# SCH_KSGER_T12_STM32_2023-10-02.net
KiCad netlist of a schematic drawn in EasyEDA
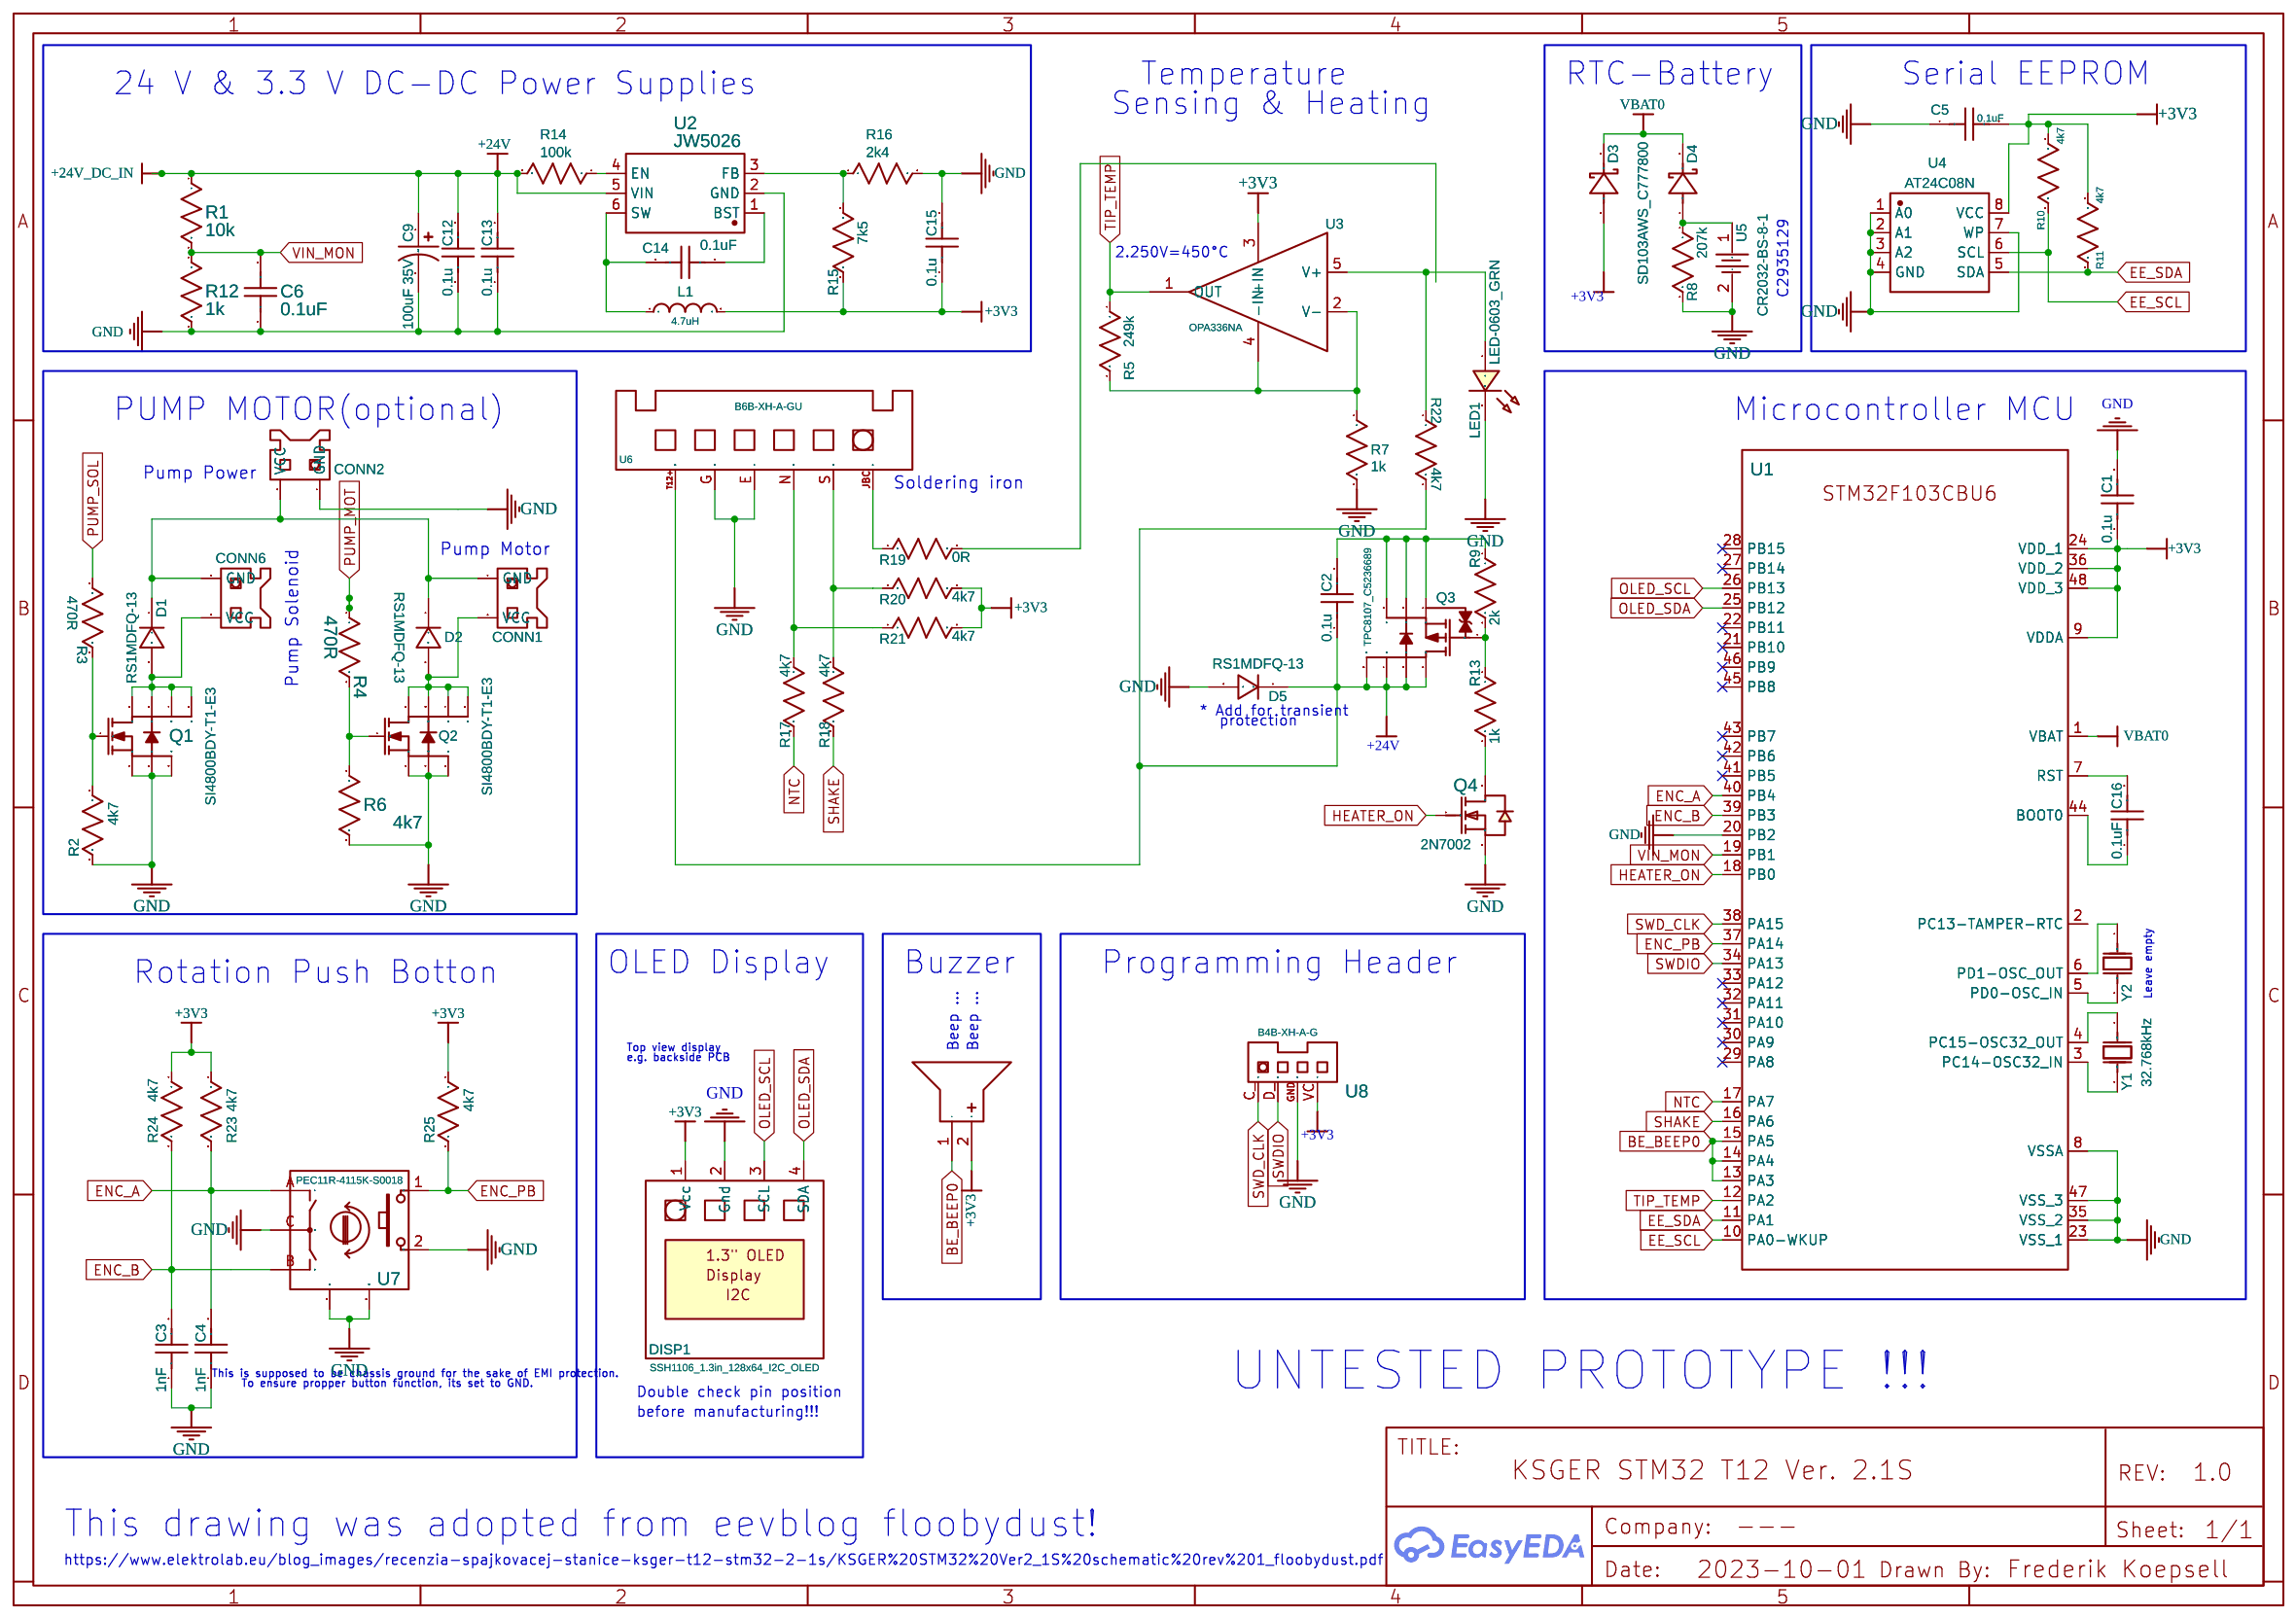
[diagram p0: schematic sheet]

(export (version "E")
  (design (tool "Eeschema 10.0.6"))
  (components
    (comp (ref "BUZZER1")
      (value "BUZZER")
      (fields (field (name "Manufacturer Part") "buzzer"))
      (libsource (lib "") (part "BUZZER"))
    )
    (comp (ref "C1") (value "0.1u") (libsource (lib "") (part "C_0603_US")))
    (comp (ref "C2") (value "0.1u") (libsource (lib "") (part "C_0603_US")))
    (comp (ref "C3") (value "1nF") (libsource (lib "") (part "C_0603_US")))
    (comp (ref "C4") (value "1nF") (libsource (lib "") (part "C_0603_US")))
    (comp (ref "C5") (value "0.1uF") (libsource (lib "") (part "C_0603_US_2")))
    (comp (ref "C6") (value "0.1uF") (libsource (lib "") (part "C_0603_US")))
    (comp (ref "C9") (value "100uF 35V") (libsource (lib "") (part "C_Tan_SMD_A_US")))
    (comp (ref "C12") (value "0.1u") (libsource (lib "") (part "C_0603_US")))
    (comp (ref "C13") (value "0.1u") (libsource (lib "") (part "C_0603_US")))
    (comp (ref "C14") (value "0.1uF") (libsource (lib "") (part "C_0603_US_1")))
    (comp (ref "C15") (value "0.1u") (libsource (lib "") (part "C_0603_US")))
    (comp (ref "C16") (value "0.1uF") (libsource (lib "") (part "C_0603_US")))
    (comp (ref "CONN1")
      (value "2_PIN_POWER_CONNECTOR_pitch_2.54_mm")
      (fields (field (name "Manufacturer Part") "XH型插座,直插,2pin,pitch=2.54mm,特思嘉ROHS"))
      (libsource (lib "") (part "2_PIN_POWER_CONNECTOR_pitch_2.54_mm"))
    )
    (comp (ref "CONN2")
      (value "2_PIN_POWER_CONNECTOR_pitch_2.54_mm")
      (fields (field (name "Manufacturer Part") "XH型插座,直插,2pin,pitch=2.54mm,特思嘉ROHS"))
      (libsource (lib "") (part "2_PIN_POWER_CONNECTOR_pitch_2.54_mm_1"))
    )
    (comp (ref "CONN6")
      (value "2_PIN_POWER_CONNECTOR_pitch_2.54_mm")
      (fields (field (name "Manufacturer Part") "XH型插座,直插,2pin,pitch=2.54mm,特思嘉ROHS"))
      (libsource (lib "") (part "2_PIN_POWER_CONNECTOR_pitch_2.54_mm"))
    )
    (comp (ref "D1")
      (value "RS1MDFQ-13")
      (fields (field (name "Manufacturer") "DIODES(美台)"))
      (libsource (lib "") (part "RS1MDFQ-13_1"))
    )
    (comp (ref "D2")
      (value "RS1MDFQ-13")
      (fields (field (name "Manufacturer") "DIODES(美台)"))
      (libsource (lib "") (part "RS1MDFQ-13_1"))
    )
    (comp (ref "D3")
      (value "SD103AWS_C777800")
      (fields (field (name "Manufacturer Part") "SD103AWS") (field (name "Manufacturer") "HT(金誉)"))
      (libsource (lib "") (part "SD103AWS_C777800"))
    )
    (comp (ref "D4")
      (value "SD103AWS_C777800")
      (fields (field (name "Manufacturer Part") "SD103AWS") (field (name "Manufacturer") "HT(金誉)"))
      (libsource (lib "") (part "SD103AWS_C777800"))
    )
    (comp (ref "D5")
      (value "RS1MDFQ-13")
      (fields (field (name "Manufacturer") "DIODES(美台)"))
      (libsource (lib "") (part "RS1MDFQ-13"))
    )
    (comp (ref "DISP1")
      (value "SSH1106_1.3in_128x64_I2C_OLED")
      (fields (field (name "BOM_Manufacturer Part") "Tribium"))
      (libsource (lib "") (part "SSH1106_1.3in_128x64_I2C_OLED"))
    )
    (comp (ref "L1")
      (value "4.7uH")
      (fields
        (field (name "Manufacturer Part") "MJC-1040T-4R7-M")
        (field (name "Manufacturer") "Me-TECH(美台高科)")
      )
      (libsource (lib "") (part "MJC-1040T-4R7-M"))
    )
    (comp (ref "LED1")
      (value "LED-0603_GRN")
      (fields
        (field (name "BOM_Manufacturer Part") "19-217/R6C-AL1M2VY/3T")
        (field (name "BOM_Supplier Part") "C72044")
      )
      (libsource (lib "") (part "LED-0603_R"))
    )
    (comp (ref "Q1")
      (value "SI4800BDY-T1-E3")
      (fields
        (field (name "Manufacturer Part") "SI4800BDY-T1-E3-VB")
        (field (name "Manufacturer") "VBsemi(微碧)")
      )
      (libsource (lib "") (part "SI4800BDY-T1-E3"))
    )
    (comp (ref "Q2")
      (value "SI4800BDY-T1-E3")
      (fields
        (field (name "Manufacturer Part") "SI4800BDY-T1-E3-VB")
        (field (name "Manufacturer") "VBsemi(微碧)")
      )
      (libsource (lib "") (part "SI4800BDY-T1-E3"))
    )
    (comp (ref "Q3")
      (value "TPC8107_C5236689")
      (fields (field (name "Manufacturer Part") "TPC8107") (field (name "Manufacturer") "UMW(广东友台半导体)"))
      (libsource (lib "") (part "TPC8107_C5236689"))
    )
    (comp (ref "Q4")
      (value "2N7002")
      (fields (field (name "BOM_Manufacturer Part") "2N7002,215") (field (name "BOM_Supplier Part") "C65189"))
      (libsource (lib "") (part "2N7002"))
    )
    (comp (ref "R1") (value "10k") (libsource (lib "") (part "R_0603_US_1")))
    (comp (ref "R2") (value "4k7") (libsource (lib "") (part "R_0603_US_1")))
    (comp (ref "R3") (value "470R") (libsource (lib "") (part "R_0603_US_1")))
    (comp (ref "R4") (value "470R") (libsource (lib "") (part "R_0603_US_1")))
    (comp (ref "R5") (value "249k") (libsource (lib "") (part "R_0603_US_1")))
    (comp (ref "R6") (value "4k7") (libsource (lib "") (part "R_0603_US_1")))
    (comp (ref "R7") (value "1k") (libsource (lib "") (part "R_0603_US_1")))
    (comp (ref "R8") (value "207k") (libsource (lib "") (part "R_0603_US_1")))
    (comp (ref "R9") (value "2k") (libsource (lib "") (part "R_0603_US_1")))
    (comp (ref "R10") (value "4k7") (libsource (lib "") (part "R_0603_US_1")))
    (comp (ref "R11") (value "4k7") (libsource (lib "") (part "R_0603_US_1")))
    (comp (ref "R12") (value "1k") (libsource (lib "") (part "R_0603_US_1")))
    (comp (ref "R13") (value "1k") (libsource (lib "") (part "R_0603_US_1")))
    (comp (ref "R14") (value "100k") (libsource (lib "") (part "R_0603_US_2")))
    (comp (ref "R15") (value "7k5") (libsource (lib "") (part "R_0603_US_1")))
    (comp (ref "R16") (value "2k4") (libsource (lib "") (part "R_0603_US")))
    (comp (ref "R17") (value "4k7") (libsource (lib "") (part "R_0603_US_1")))
    (comp (ref "R18") (value "4k7") (libsource (lib "") (part "R_0603_US_1")))
    (comp (ref "R19") (value "0R") (libsource (lib "") (part "R_0603_US")))
    (comp (ref "R20") (value "4k7") (libsource (lib "") (part "R_0603_US")))
    (comp (ref "R21") (value "4k7") (libsource (lib "") (part "R_0603_US")))
    (comp (ref "R22") (value "4k7") (libsource (lib "") (part "R_0603_US_1")))
    (comp (ref "R23") (value "4k7") (libsource (lib "") (part "R_0603_US_1")))
    (comp (ref "R24") (value "4k7") (libsource (lib "") (part "R_0603_US_1")))
    (comp (ref "R25") (value "4k7") (libsource (lib "") (part "R_0603_US_1")))
    (comp (ref "U1")
      (value "STM32F103CBU6")
      (fields (field (name "Manufacturer Part") "STM32F401CCU6") (field (name "Manufacturer") "ST"))
      (libsource (lib "") (part "STM32F103C8T6"))
    )
    (comp (ref "U2")
      (value "JW5026")
      (fields (field (name "Manufacturer") "Joulwatt(杰华特)"))
      (libsource (lib "") (part "JW5026"))
    )
    (comp (ref "U3")
      (value "OPA336NA")
      (fields (field (name "Manufacturer Part") "OPA336NA/3K") (field (name "Manufacturer") "TI(德州仪器)"))
      (libsource (lib "") (part "OPA336NA"))
    )
    (comp (ref "U4")
      (value "AT24C08N")
      (fields (field (name "Manufacturer") "HGSEMI"))
      (libsource (lib "") (part "AT24C08N"))
    )
    (comp (ref "U5") (value "CR2032-BS-8-1") (libsource (lib "") (part "CR2032-BS-8-1_C2935129")))
    (comp (ref "U6")
      (value "B6B-XH-A-GU")
      (fields (field (name "Manufacturer") "JST"))
      (libsource (lib "") (part "B6B-XH-A-GU"))
    )
    (comp (ref "U7") (value "PEC11R-4115K-S0018") (libsource (lib "") (part "PEC11R-4115K-S0018")))
    (comp (ref "U8")
      (value "B4B-XH-A-G")
      (fields (field (name "Manufacturer") "JST"))
      (libsource (lib "") (part "B4B-XH-A-G"))
    )
    (comp (ref "Y1")
      (value "32.768kHz")
      (fields
        (field (name "Manufacturer Part") "NX1610SA-32.768KHZ-EXS00A-MU00658")
        (field (name "Manufacturer") "NDK")
      )
      (libsource (lib "") (part "NX1610SA-32.768KHZ-EXS00A-MU00658"))
    )
    (comp (ref "Y2")
      (value "32.768kHz")
      (fields
        (field (name "Manufacturer Part") "NX1610SA-32.768KHZ-EXS00A-MU00658")
        (field (name "Manufacturer") "NDK")
      )
      (libsource (lib "") (part "NX1610SA-32.768KHZ-EXS00A-MU00658"))
    )
  )
  (nets
    (net (code "1") (name "+3V3") (class "Default")
      (node (ref "BUZZER1") (pin "2") (pinfunction "+_2") (pintype "unspecified"))
      (node (ref "C1") (pin "1") (pinfunction "1_1") (pintype "unspecified"))
      (node (ref "C15") (pin "1") (pinfunction "1_1") (pintype "unspecified"))
      (node (ref "C5") (pin "2") (pinfunction "2_2") (pintype "unspecified"))
      (node (ref "D3") (pin "1") (pinfunction "A_1") (pintype "unspecified"))
      (node (ref "DISP1") (pin "1") (pinfunction "Vcc_1") (pintype "unspecified"))
      (node (ref "L1") (pin "2") (pinfunction "2_2") (pintype "unspecified"))
      (node (ref "R10") (pin "1") (pinfunction "1_1") (pintype "unspecified"))
      (node (ref "R11") (pin "1") (pinfunction "1_1") (pintype "unspecified"))
      (node (ref "R15") (pin "2") (pinfunction "2_2") (pintype "unspecified"))
      (node (ref "R20") (pin "2") (pinfunction "2_2") (pintype "unspecified"))
      (node (ref "R21") (pin "2") (pinfunction "2_2") (pintype "unspecified"))
      (node (ref "R23") (pin "1") (pinfunction "1_1") (pintype "unspecified"))
      (node (ref "R24") (pin "1") (pinfunction "1_1") (pintype "unspecified"))
      (node (ref "R25") (pin "1") (pinfunction "1_1") (pintype "unspecified"))
      (node (ref "U1") (pin "24") (pinfunction "VDD_1_24") (pintype "unspecified"))
      (node (ref "U1") (pin "36") (pinfunction "VDD_2_36") (pintype "unspecified"))
      (node (ref "U1") (pin "48") (pinfunction "VDD_3_48") (pintype "unspecified"))
      (node (ref "U1") (pin "9") (pinfunction "VDDA_9") (pintype "unspecified"))
      (node (ref "U3") (pin "3") (pinfunction "+IN_3") (pintype "unspecified"))
      (node (ref "U4") (pin "8") (pinfunction "VCC_8") (pintype "unspecified"))
      (node (ref "U8") (pin "VC") (pinfunction "4_VC") (pintype "unspecified"))
    )
    (net (code "2") (name "+24V") (class "Default")
      (node (ref "C12") (pin "2") (pinfunction "2_2") (pintype "unspecified"))
      (node (ref "C13") (pin "2") (pinfunction "2_2") (pintype "unspecified"))
      (node (ref "C2") (pin "1") (pinfunction "1_1") (pintype "unspecified"))
      (node (ref "C9") (pin "1") (pinfunction "1_1") (pintype "unspecified"))
      (node (ref "D5") (pin "1") (pinfunction "1_1") (pintype "unspecified"))
      (node (ref "Q3") (pin "5") (pinfunction "D_5") (pintype "unspecified"))
      (node (ref "Q3") (pin "6") (pinfunction "D_6") (pintype "unspecified"))
      (node (ref "Q3") (pin "7") (pinfunction "D_7") (pintype "unspecified"))
      (node (ref "Q3") (pin "8") (pinfunction "D_8") (pintype "unspecified"))
      (node (ref "R1") (pin "1") (pinfunction "1_1") (pintype "unspecified"))
      (node (ref "R14") (pin "2") (pinfunction "2_2") (pintype "unspecified"))
      (node (ref "R22") (pin "2") (pinfunction "2_2") (pintype "unspecified"))
      (node (ref "U2") (pin "5") (pinfunction "VIN_5") (pintype "unspecified"))
      (node (ref "U6") (pin "T12+") (pinfunction "6_T12+") (pintype "unspecified"))
    )
    (net (code "3") (name "BE_BEEP0") (class "Default")
      (node (ref "BUZZER1") (pin "1") (pinfunction "-_1") (pintype "unspecified"))
      (node (ref "U1") (pin "13") (pinfunction "PA3_13") (pintype "unspecified"))
      (node (ref "U1") (pin "14") (pinfunction "PA4_14") (pintype "unspecified"))
      (node (ref "U1") (pin "15") (pinfunction "PA5_15") (pintype "unspecified"))
    )
    (net (code "4") (name "EE_SCL") (class "Default")
      (node (ref "R10") (pin "2") (pinfunction "2_2") (pintype "unspecified"))
      (node (ref "U1") (pin "10") (pinfunction "PA0-WKUP_10") (pintype "unspecified"))
      (node (ref "U4") (pin "6") (pinfunction "SCL_6") (pintype "unspecified"))
    )
    (net (code "5") (name "EE_SDA") (class "Default")
      (node (ref "R11") (pin "2") (pinfunction "2_2") (pintype "unspecified"))
      (node (ref "U1") (pin "11") (pinfunction "PA1_11") (pintype "unspecified"))
      (node (ref "U4") (pin "5") (pinfunction "SDA_5") (pintype "unspecified"))
    )
    (net (code "6") (name "ENC_A") (class "Default")
      (node (ref "C4") (pin "2") (pinfunction "2_2") (pintype "unspecified"))
      (node (ref "R23") (pin "2") (pinfunction "2_2") (pintype "unspecified"))
      (node (ref "U1") (pin "40") (pinfunction "PB4_40") (pintype "unspecified"))
      (node (ref "U7") (pin "A") (pinfunction "A_A") (pintype "unspecified"))
    )
    (net (code "7") (name "ENC_B") (class "Default")
      (node (ref "C3") (pin "2") (pinfunction "2_2") (pintype "unspecified"))
      (node (ref "R24") (pin "2") (pinfunction "2_2") (pintype "unspecified"))
      (node (ref "U1") (pin "39") (pinfunction "PB3_39") (pintype "unspecified"))
      (node (ref "U7") (pin "B") (pinfunction "B_B") (pintype "unspecified"))
    )
    (net (code "8") (name "ENC_PB") (class "Default")
      (node (ref "R25") (pin "2") (pinfunction "2_2") (pintype "unspecified"))
      (node (ref "U1") (pin "37") (pinfunction "PA14_37") (pintype "unspecified"))
      (node (ref "U7") (pin "1") (pinfunction "1_1") (pintype "unspecified"))
    )
    (net (code "9") (name "GND") (class "Default")
      (node (ref "C1") (pin "2") (pinfunction "2_2") (pintype "unspecified"))
      (node (ref "C12") (pin "1") (pinfunction "1_1") (pintype "unspecified"))
      (node (ref "C13") (pin "1") (pinfunction "1_1") (pintype "unspecified"))
      (node (ref "C15") (pin "2") (pinfunction "2_2") (pintype "unspecified"))
      (node (ref "C3") (pin "1") (pinfunction "1_1") (pintype "unspecified"))
      (node (ref "C4") (pin "1") (pinfunction "1_1") (pintype "unspecified"))
      (node (ref "C5") (pin "1") (pinfunction "1_1") (pintype "unspecified"))
      (node (ref "C6") (pin "1") (pinfunction "1_1") (pintype "unspecified"))
      (node (ref "C9") (pin "2") (pinfunction "2_2") (pintype "unspecified"))
      (node (ref "CONN2") (pin "1") (pinfunction "GND_1") (pintype "unspecified"))
      (node (ref "D5") (pin "2") (pinfunction "2_2") (pintype "unspecified"))
      (node (ref "DISP1") (pin "2") (pinfunction "Gnd_2") (pintype "unspecified"))
      (node (ref "LED1") (pin "2") (pinfunction "2_2") (pintype "unspecified"))
      (node (ref "Q1") (pin "1") (pinfunction "S_1") (pintype "unspecified"))
      (node (ref "Q1") (pin "2") (pinfunction "S_2") (pintype "unspecified"))
      (node (ref "Q1") (pin "3") (pinfunction "S_3") (pintype "unspecified"))
      (node (ref "Q2") (pin "1") (pinfunction "S_1") (pintype "unspecified"))
      (node (ref "Q2") (pin "2") (pinfunction "S_2") (pintype "unspecified"))
      (node (ref "Q2") (pin "3") (pinfunction "S_3") (pintype "unspecified"))
      (node (ref "Q4") (pin "2") (pinfunction "S_2") (pintype "unspecified"))
      (node (ref "R12") (pin "2") (pinfunction "2_2") (pintype "unspecified"))
      (node (ref "R16") (pin "2") (pinfunction "2_2") (pintype "unspecified"))
      (node (ref "R2") (pin "2") (pinfunction "2_2") (pintype "unspecified"))
      (node (ref "R6") (pin "2") (pinfunction "2_2") (pintype "unspecified"))
      (node (ref "R7") (pin "2") (pinfunction "2_2") (pintype "unspecified"))
      (node (ref "R8") (pin "2") (pinfunction "2_2") (pintype "unspecified"))
      (node (ref "U1") (pin "20") (pinfunction "PB2_20") (pintype "unspecified"))
      (node (ref "U1") (pin "23") (pinfunction "VSS_1_23") (pintype "unspecified"))
      (node (ref "U1") (pin "35") (pinfunction "VSS_2_35") (pintype "unspecified"))
      (node (ref "U1") (pin "47") (pinfunction "VSS_3_47") (pintype "unspecified"))
      (node (ref "U1") (pin "8") (pinfunction "VSSA_8") (pintype "unspecified"))
      (node (ref "U2") (pin "2") (pinfunction "GND_2") (pintype "unspecified"))
      (node (ref "U4") (pin "1") (pinfunction "A0_1") (pintype "unspecified"))
      (node (ref "U4") (pin "2") (pinfunction "A1_2") (pintype "unspecified"))
      (node (ref "U4") (pin "3") (pinfunction "A2_3") (pintype "unspecified"))
      (node (ref "U4") (pin "4") (pinfunction "GND_4") (pintype "unspecified"))
      (node (ref "U4") (pin "7") (pinfunction "WP_7") (pintype "unspecified"))
      (node (ref "U5") (pin "2") (pinfunction "-_2") (pintype "input"))
      (node (ref "U6") (pin "E") (pinfunction "4_E") (pintype "unspecified"))
      (node (ref "U6") (pin "G") (pinfunction "5_G") (pintype "unspecified"))
      (node (ref "U7") (pin "2") (pinfunction "2_2") (pintype "unspecified"))
      (node (ref "U7") (pin "C") (pinfunction "C_C") (pintype "unspecified"))
      (node (ref "U7") (pin "MT1") (pinfunction "MT1_MT1") (pintype "unspecified"))
      (node (ref "U7") (pin "MT2") (pinfunction "MT2_MT2") (pintype "unspecified"))
      (node (ref "U8") (pin "GND") (pinfunction "3_GND") (pintype "unspecified"))
    )
    (net (code "10") (name "HEATER_ON") (class "Default")
      (node (ref "Q4") (pin "1") (pinfunction "G_1") (pintype "unspecified"))
      (node (ref "U1") (pin "18") (pinfunction "PB0_18") (pintype "unspecified"))
    )
    (net (code "11") (name "NTC") (class "Default")
      (node (ref "R17") (pin "2") (pinfunction "2_2") (pintype "unspecified"))
      (node (ref "U1") (pin "17") (pinfunction "PA7_17") (pintype "unspecified"))
    )
    (net (code "12") (name "Net-(C2-Pad2)") (class "Default")
      (node (ref "C2") (pin "2") (pinfunction "2_2") (pintype "unspecified"))
      (node (ref "Q3") (pin "1") (pinfunction "S_1") (pintype "unspecified"))
      (node (ref "Q3") (pin "2") (pinfunction "S_2") (pintype "unspecified"))
      (node (ref "Q3") (pin "3") (pinfunction "S_3") (pintype "unspecified"))
      (node (ref "R9") (pin "1") (pinfunction "1_1") (pintype "unspecified"))
    )
    (net (code "13") (name "Net-(CONN1-GND)") (class "Default")
      (node (ref "CONN1") (pin "1") (pinfunction "GND_1") (pintype "unspecified"))
      (node (ref "CONN2") (pin "2") (pinfunction "VCC_2") (pintype "unspecified"))
      (node (ref "CONN6") (pin "1") (pinfunction "GND_1") (pintype "unspecified"))
      (node (ref "D1") (pin "1") (pinfunction "1_1") (pintype "unspecified"))
      (node (ref "D2") (pin "1") (pinfunction "1_1") (pintype "unspecified"))
    )
    (net (code "14") (name "Net-(CONN1-VCC)") (class "Default")
      (node (ref "CONN1") (pin "2") (pinfunction "VCC_2") (pintype "unspecified"))
      (node (ref "D2") (pin "2") (pinfunction "2_2") (pintype "unspecified"))
      (node (ref "Q2") (pin "5") (pinfunction "D_5") (pintype "unspecified"))
      (node (ref "Q2") (pin "6") (pinfunction "D_6") (pintype "unspecified"))
      (node (ref "Q2") (pin "7") (pinfunction "D_7") (pintype "unspecified"))
      (node (ref "Q2") (pin "8") (pinfunction "D_8") (pintype "unspecified"))
    )
    (net (code "15") (name "Net-(CONN6-VCC)") (class "Default")
      (node (ref "CONN6") (pin "2") (pinfunction "VCC_2") (pintype "unspecified"))
      (node (ref "D1") (pin "2") (pinfunction "2_2") (pintype "unspecified"))
      (node (ref "Q1") (pin "5") (pinfunction "D_5") (pintype "unspecified"))
      (node (ref "Q1") (pin "6") (pinfunction "D_6") (pintype "unspecified"))
      (node (ref "Q1") (pin "7") (pinfunction "D_7") (pintype "unspecified"))
      (node (ref "Q1") (pin "8") (pinfunction "D_8") (pintype "unspecified"))
    )
    (net (code "16") (name "Net-(D4-A)") (class "Default")
      (node (ref "D4") (pin "1") (pinfunction "A_1") (pintype "unspecified"))
      (node (ref "R8") (pin "1") (pinfunction "1_1") (pintype "unspecified"))
      (node (ref "U5") (pin "1") (pinfunction "+_1") (pintype "input"))
    )
    (net (code "17") (name "Net-(Q1-G)") (class "Default")
      (node (ref "Q1") (pin "4") (pinfunction "G_4") (pintype "unspecified"))
      (node (ref "R2") (pin "1") (pinfunction "1_1") (pintype "unspecified"))
      (node (ref "R3") (pin "2") (pinfunction "2_2") (pintype "unspecified"))
    )
    (net (code "18") (name "Net-(Q2-G)") (class "Default")
      (node (ref "Q2") (pin "4") (pinfunction "G_4") (pintype "unspecified"))
      (node (ref "R4") (pin "2") (pinfunction "2_2") (pintype "unspecified"))
      (node (ref "R6") (pin "1") (pinfunction "1_1") (pintype "unspecified"))
    )
    (net (code "19") (name "Net-(Q3-G)") (class "Default")
      (node (ref "Q3") (pin "4") (pinfunction "G_4") (pintype "unspecified"))
      (node (ref "R13") (pin "1") (pinfunction "1_1") (pintype "unspecified"))
      (node (ref "R9") (pin "2") (pinfunction "2_2") (pintype "unspecified"))
    )
    (net (code "20") (name "Net-(Q4-D)") (class "Default")
      (node (ref "Q4") (pin "3") (pinfunction "D_3") (pintype "unspecified"))
      (node (ref "R13") (pin "2") (pinfunction "2_2") (pintype "unspecified"))
    )
    (net (code "21") (name "Net-(U1-BOOT0)") (class "Default")
      (node (ref "C16") (pin "1") (pinfunction "1_1") (pintype "unspecified"))
      (node (ref "U1") (pin "44") (pinfunction "BOOT0_44") (pintype "unspecified"))
    )
    (net (code "22") (name "Net-(U1-PC14-OSC32_IN)") (class "Default")
      (node (ref "U1") (pin "3") (pinfunction "PC14-OSC32_IN_3") (pintype "unspecified"))
      (node (ref "Y1") (pin "2") (pinfunction "OSC2_2") (pintype "input"))
    )
    (net (code "23") (name "Net-(U1-PC15-OSC32_OUT)") (class "Default")
      (node (ref "U1") (pin "4") (pinfunction "PC15-OSC32_OUT_4") (pintype "unspecified"))
      (node (ref "Y1") (pin "1") (pinfunction "OSC1_1") (pintype "input"))
    )
    (net (code "24") (name "Net-(U1-PD0-OSC_IN)") (class "Default")
      (node (ref "U1") (pin "5") (pinfunction "PD0-OSC_IN_5") (pintype "unspecified"))
      (node (ref "Y2") (pin "2") (pinfunction "OSC2_2") (pintype "input"))
    )
    (net (code "25") (name "Net-(U1-PD1-OSC_OUT)") (class "Default")
      (node (ref "U1") (pin "6") (pinfunction "PD1-OSC_OUT_6") (pintype "unspecified"))
      (node (ref "Y2") (pin "1") (pinfunction "OSC1_1") (pintype "input"))
    )
    (net (code "26") (name "Net-(U1-RST)") (class "Default")
      (node (ref "C16") (pin "2") (pinfunction "2_2") (pintype "unspecified"))
      (node (ref "U1") (pin "7") (pinfunction "RST_7") (pintype "unspecified"))
    )
    (net (code "27") (name "Net-(U2-BST)") (class "Default")
      (node (ref "C14") (pin "1") (pinfunction "1_1") (pintype "unspecified"))
      (node (ref "U2") (pin "1") (pinfunction "BST_1") (pintype "unspecified"))
    )
    (net (code "28") (name "Net-(U2-EN)") (class "Default")
      (node (ref "R14") (pin "1") (pinfunction "1_1") (pintype "unspecified"))
      (node (ref "U2") (pin "4") (pinfunction "EN_4") (pintype "unspecified"))
    )
    (net (code "29") (name "Net-(U2-FB)") (class "Default")
      (node (ref "R15") (pin "1") (pinfunction "1_1") (pintype "unspecified"))
      (node (ref "R16") (pin "1") (pinfunction "1_1") (pintype "unspecified"))
      (node (ref "U2") (pin "3") (pinfunction "FB_3") (pintype "unspecified"))
    )
    (net (code "30") (name "Net-(U2-SW)") (class "Default")
      (node (ref "C14") (pin "2") (pinfunction "2_2") (pintype "unspecified"))
      (node (ref "L1") (pin "1") (pinfunction "1_1") (pintype "unspecified"))
      (node (ref "U2") (pin "6") (pinfunction "SW_6") (pintype "unspecified"))
    )
    (net (code "31") (name "Net-(U3--IN)") (class "Default")
      (node (ref "R5") (pin "2") (pinfunction "2_2") (pintype "unspecified"))
      (node (ref "R7") (pin "1") (pinfunction "1_1") (pintype "unspecified"))
      (node (ref "U3") (pin "2") (pinfunction "V-_2") (pintype "unspecified"))
      (node (ref "U3") (pin "4") (pinfunction "-IN_4") (pintype "unspecified"))
    )
    (net (code "32") (name "Net-(U3-V+)") (class "Default")
      (node (ref "LED1") (pin "1") (pinfunction "1_1") (pintype "unspecified"))
      (node (ref "R22") (pin "1") (pinfunction "1_1") (pintype "unspecified"))
      (node (ref "U3") (pin "5") (pinfunction "V+_5") (pintype "unspecified"))
    )
    (net (code "33") (name "Net-(U6-1)") (class "Default")
      (node (ref "R19") (pin "1") (pinfunction "1_1") (pintype "unspecified"))
      (node (ref "U6") (pin "JBC") (pinfunction "1_JBC") (pintype "unspecified"))
    )
    (net (code "34") (name "Net-(U6-2)") (class "Default")
      (node (ref "R18") (pin "1") (pinfunction "1_1") (pintype "unspecified"))
      (node (ref "R20") (pin "1") (pinfunction "1_1") (pintype "unspecified"))
      (node (ref "U6") (pin "S") (pinfunction "2_S") (pintype "unspecified"))
    )
    (net (code "35") (name "Net-(U6-3)") (class "Default")
      (node (ref "R17") (pin "1") (pinfunction "1_1") (pintype "unspecified"))
      (node (ref "R21") (pin "1") (pinfunction "1_1") (pintype "unspecified"))
      (node (ref "U6") (pin "N") (pinfunction "3_N") (pintype "unspecified"))
    )
    (net (code "36") (name "OLED_SCL") (class "Default")
      (node (ref "DISP1") (pin "3") (pinfunction "SCL_3") (pintype "unspecified"))
      (node (ref "U1") (pin "26") (pinfunction "PB13_26") (pintype "unspecified"))
    )
    (net (code "37") (name "OLED_SDA") (class "Default")
      (node (ref "DISP1") (pin "4") (pinfunction "SDA_4") (pintype "unspecified"))
      (node (ref "U1") (pin "25") (pinfunction "PB12_25") (pintype "unspecified"))
    )
    (net (code "38") (name "PUMP_MOT") (class "Default")
      (node (ref "R4") (pin "1") (pinfunction "1_1") (pintype "unspecified"))
    )
    (net (code "39") (name "PUMP_SOL") (class "Default")
      (node (ref "R3") (pin "1") (pinfunction "1_1") (pintype "unspecified"))
    )
    (net (code "40") (name "SHAKE") (class "Default")
      (node (ref "R18") (pin "2") (pinfunction "2_2") (pintype "unspecified"))
      (node (ref "U1") (pin "16") (pinfunction "PA6_16") (pintype "unspecified"))
    )
    (net (code "41") (name "SWDIO") (class "Default")
      (node (ref "U1") (pin "34") (pinfunction "PA13_34") (pintype "unspecified"))
      (node (ref "U8") (pin "D_") (pinfunction "2_D_") (pintype "unspecified"))
    )
    (net (code "42") (name "SWD_CLK") (class "Default")
      (node (ref "U1") (pin "38") (pinfunction "PA15_38") (pintype "unspecified"))
      (node (ref "U8") (pin "C_") (pinfunction "1_C_") (pintype "unspecified"))
    )
    (net (code "43") (name "TIP_TEMP") (class "Default")
      (node (ref "R5") (pin "1") (pinfunction "1_1") (pintype "unspecified"))
      (node (ref "U1") (pin "12") (pinfunction "PA2_12") (pintype "unspecified"))
      (node (ref "U3") (pin "1") (pinfunction "OUT_1") (pintype "unspecified"))
    )
    (net (code "44") (name "VBAT0") (class "Default")
      (node (ref "D3") (pin "2") (pinfunction "K_2") (pintype "unspecified"))
      (node (ref "D4") (pin "2") (pinfunction "K_2") (pintype "unspecified"))
      (node (ref "U1") (pin "1") (pinfunction "VBAT_1") (pintype "unspecified"))
    )
    (net (code "45") (name "VIN_MON") (class "Default")
      (node (ref "C6") (pin "2") (pinfunction "2_2") (pintype "unspecified"))
      (node (ref "R1") (pin "2") (pinfunction "2_2") (pintype "unspecified"))
      (node (ref "R12") (pin "1") (pinfunction "1_1") (pintype "unspecified"))
      (node (ref "U1") (pin "19") (pinfunction "PB1_19") (pintype "unspecified"))
    )
    (net (code "46") (name "unconnected-(R19-Pad2)") (class "Default")
      (node (ref "R19") (pin "2") (pinfunction "2_2") (pintype "unspecified"))
    )
    (net (code "47") (name "unconnected-(U1-PA8-Pad29)") (class "Default")
      (node (ref "U1") (pin "29") (pinfunction "PA8_29") (pintype "unspecified+no_connect"))
    )
    (net (code "48") (name "unconnected-(U1-PA9-Pad30)") (class "Default")
      (node (ref "U1") (pin "30") (pinfunction "PA9_30") (pintype "unspecified+no_connect"))
    )
    (net (code "49") (name "unconnected-(U1-PA10-Pad31)") (class "Default")
      (node (ref "U1") (pin "31") (pinfunction "PA10_31") (pintype "unspecified+no_connect"))
    )
    (net (code "50") (name "unconnected-(U1-PA11-Pad32)") (class "Default")
      (node (ref "U1") (pin "32") (pinfunction "PA11_32") (pintype "unspecified+no_connect"))
    )
    (net (code "51") (name "unconnected-(U1-PA12-Pad33)") (class "Default")
      (node (ref "U1") (pin "33") (pinfunction "PA12_33") (pintype "unspecified+no_connect"))
    )
    (net (code "52") (name "unconnected-(U1-PB5-Pad41)") (class "Default")
      (node (ref "U1") (pin "41") (pinfunction "PB5_41") (pintype "unspecified+no_connect"))
    )
    (net (code "53") (name "unconnected-(U1-PB6-Pad42)") (class "Default")
      (node (ref "U1") (pin "42") (pinfunction "PB6_42") (pintype "unspecified+no_connect"))
    )
    (net (code "54") (name "unconnected-(U1-PB7-Pad43)") (class "Default")
      (node (ref "U1") (pin "43") (pinfunction "PB7_43") (pintype "unspecified+no_connect"))
    )
    (net (code "55") (name "unconnected-(U1-PB8-Pad45)") (class "Default")
      (node (ref "U1") (pin "45") (pinfunction "PB8_45") (pintype "unspecified+no_connect"))
    )
    (net (code "56") (name "unconnected-(U1-PB9-Pad46)") (class "Default")
      (node (ref "U1") (pin "46") (pinfunction "PB9_46") (pintype "unspecified+no_connect"))
    )
    (net (code "57") (name "unconnected-(U1-PB10-Pad21)") (class "Default")
      (node (ref "U1") (pin "21") (pinfunction "PB10_21") (pintype "unspecified+no_connect"))
    )
    (net (code "58") (name "unconnected-(U1-PB11-Pad22)") (class "Default")
      (node (ref "U1") (pin "22") (pinfunction "PB11_22") (pintype "unspecified+no_connect"))
    )
    (net (code "59") (name "unconnected-(U1-PB14-Pad27)") (class "Default")
      (node (ref "U1") (pin "27") (pinfunction "PB14_27") (pintype "unspecified+no_connect"))
    )
    (net (code "60") (name "unconnected-(U1-PB15-Pad28)") (class "Default")
      (node (ref "U1") (pin "28") (pinfunction "PB15_28") (pintype "unspecified+no_connect"))
    )
    (net (code "61") (name "unconnected-(U1-PC13-TAMPER-RTC-Pad2)") (class "Default")
      (node (ref "U1") (pin "2") (pinfunction "PC13-TAMPER-RTC_2") (pintype "unspecified"))
    )
  )
)
